# BrainControlBoard.net
KiCad netlist of a schematic drawn in EAGLE
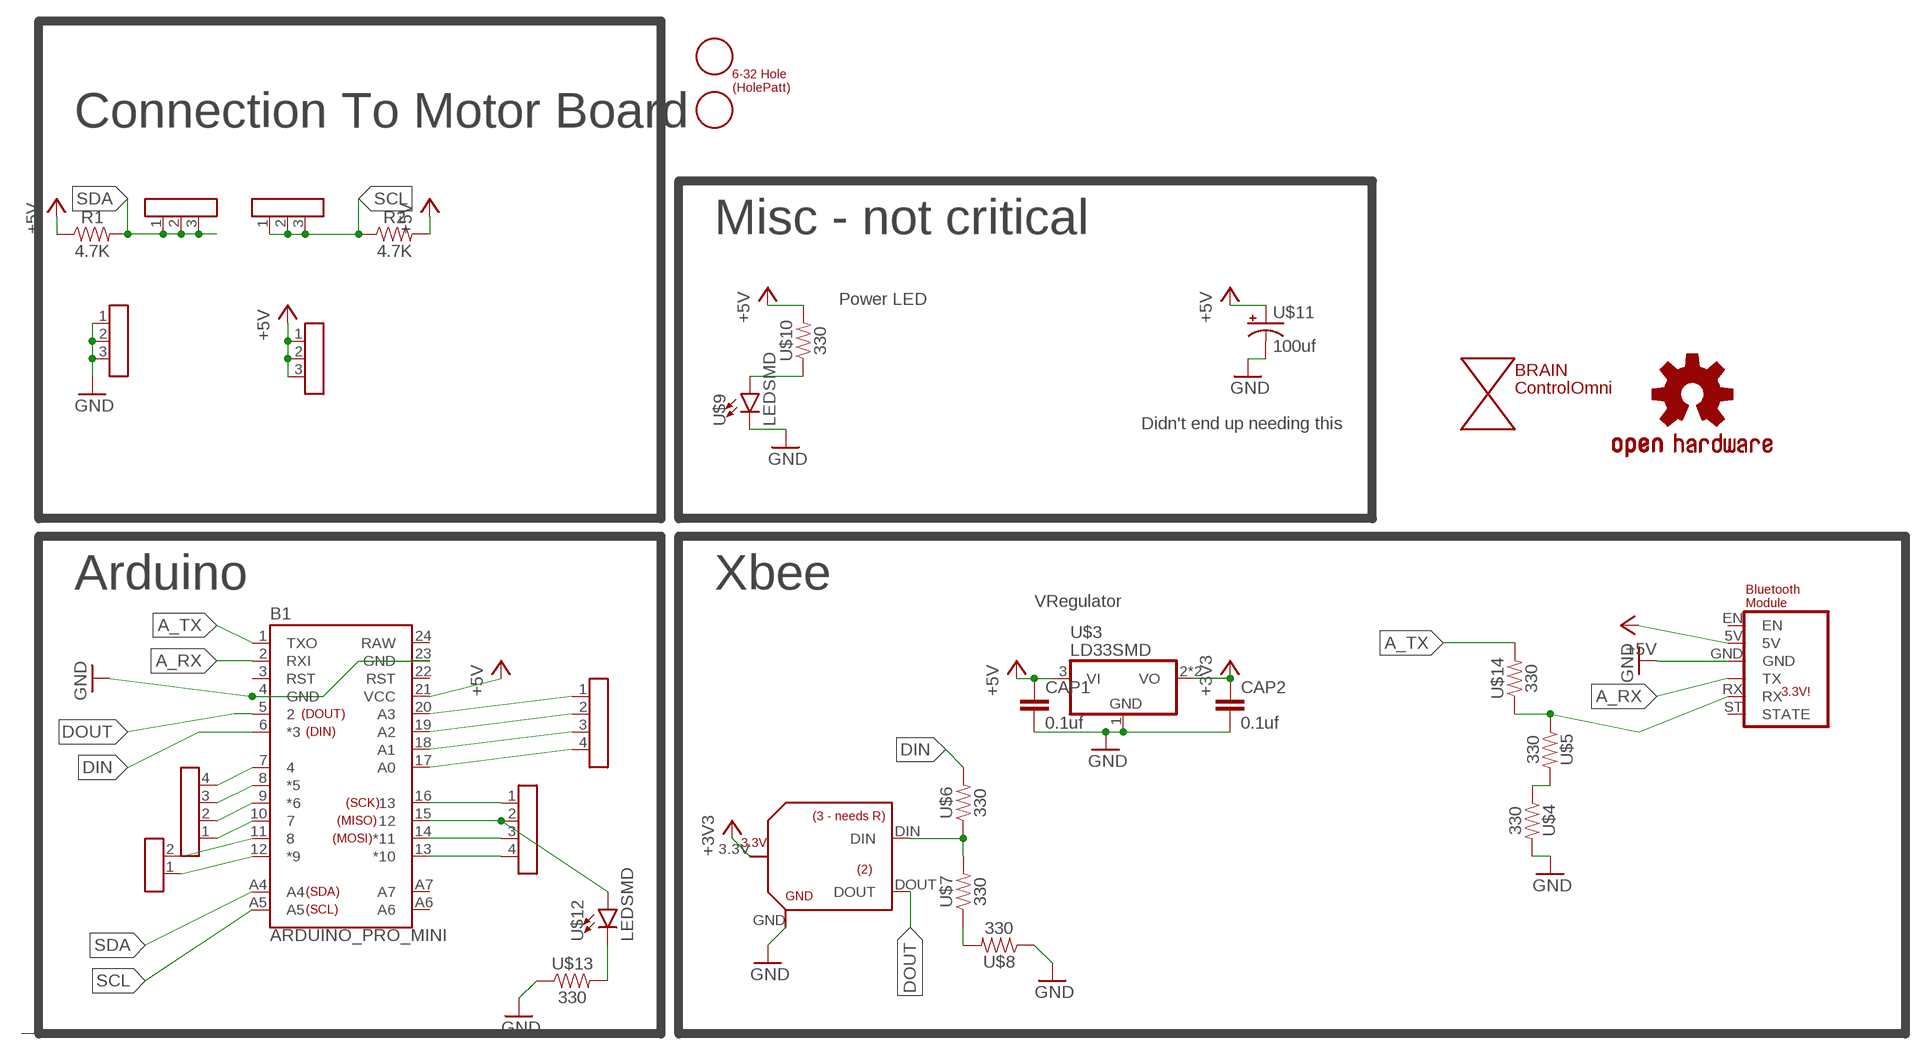
[diagram p0: schematic, sheet 1]

(export (version "E")
  (design (tool "Eeschema 10.0.6"))
  (components
    (comp (ref "B1")
      (value "ARDUINO_PRO_MINI")
      (footprint "eagle-import:ARDUINO_PRO_MINI")
      (libsource (lib "eagle-import") (part "ARDUINO_PRO_MINI"))
    )
    (comp (ref "BRAIN")
      (value "ControlOmni")
      (footprint "eagle-import:ANNOTATION")
      (libsource (lib "eagle-import") (part "ANNOTATION"))
    )
    (comp (ref "CAP1")
      (value "0.1uf")
      (footprint "eagle-import:C1206")
      (libsource (lib "eagle-import") (part "CAP_SMCAP"))
    )
    (comp (ref "CAP2")
      (value "0.1uf")
      (footprint "eagle-import:C1206")
      (libsource (lib "eagle-import") (part "CAP_SMCAP"))
    )
    (comp (ref "LOGO1")
      (value "OSHW-LOGOM")
      (footprint "eagle-import:OSHW-LOGO-M")
      (libsource (lib "eagle-import") (part "OSHW-LOGOM"))
    )
    (comp (ref "R1")
      (value "4.7K")
      (footprint "eagle-import:R1206")
      (libsource (lib "eagle-import") (part "RESISTORSMD"))
    )
    (comp (ref "R2")
      (value "4.7K")
      (footprint "eagle-import:R1206")
      (libsource (lib "eagle-import") (part "RESISTORSMD"))
    )
    (comp (ref "U$1")
      (value "BLUETOOTH")
      (footprint "eagle-import:BLUETOOTH")
      (libsource (lib "eagle-import") (part "BLUETOOTH"))
    )
    (comp (ref "U$2")
      (value "XBEE_BOUT")
      (footprint "eagle-import:XBEE_BOUT")
      (libsource (lib "eagle-import") (part "XBEE_BOUT"))
    )
    (comp (ref "U$3")
      (value "LD33SMD")
      (footprint "eagle-import:SOT223")
      (libsource (lib "eagle-import") (part "LD33SMD"))
    )
    (comp (ref "U$4")
      (value "330")
      (footprint "eagle-import:R1206")
      (libsource (lib "eagle-import") (part "RESISTORSMD"))
    )
    (comp (ref "U$5")
      (value "330")
      (footprint "eagle-import:R1206")
      (libsource (lib "eagle-import") (part "RESISTORSMD"))
    )
    (comp (ref "U$6")
      (value "330")
      (footprint "eagle-import:R1206")
      (libsource (lib "eagle-import") (part "RESISTORSMD"))
    )
    (comp (ref "U$7")
      (value "330")
      (footprint "eagle-import:R1206")
      (libsource (lib "eagle-import") (part "RESISTORSMD"))
    )
    (comp (ref "U$8")
      (value "330")
      (footprint "eagle-import:R1206")
      (libsource (lib "eagle-import") (part "RESISTORSMD"))
    )
    (comp (ref "U$9")
      (value "LEDSMD")
      (footprint "eagle-import:LED_SMD")
      (libsource (lib "eagle-import") (part "LEDSMD"))
    )
    (comp (ref "U$10")
      (value "330")
      (footprint "eagle-import:R1206")
      (libsource (lib "eagle-import") (part "RESISTORSMD"))
    )
    (comp (ref "U$11")
      (value "100uf")
      (footprint "eagle-import:CAP_E")
      (libsource (lib "eagle-import") (part "CAP_EMED"))
    )
    (comp (ref "U$12")
      (value "LEDSMD")
      (footprint "eagle-import:LED_SMD")
      (libsource (lib "eagle-import") (part "LEDSMD"))
    )
    (comp (ref "U$13")
      (value "330")
      (footprint "eagle-import:R1206")
      (libsource (lib "eagle-import") (part "RESISTORSMD"))
    )
    (comp (ref "U$14")
      (value "330")
      (footprint "eagle-import:R1206")
      (libsource (lib "eagle-import") (part "RESISTORSMD"))
    )
    (comp (ref "U$15")
      (value "3XHEADER")
      (footprint "eagle-import:3XHEADER")
      (libsource (lib "eagle-import") (part "3XHEADER"))
    )
    (comp (ref "U$16")
      (value "3XHEADER")
      (footprint "eagle-import:3XHEADER")
      (libsource (lib "eagle-import") (part "3XHEADER"))
    )
    (comp (ref "U$17")
      (value "3XHEADER")
      (footprint "eagle-import:3XHEADER")
      (libsource (lib "eagle-import") (part "3XHEADER"))
    )
    (comp (ref "U$18")
      (value "3XHEADER")
      (footprint "eagle-import:3XHEADER")
      (libsource (lib "eagle-import") (part "3XHEADER"))
    )
    (comp (ref "U$19")
      (value "4XHEADER")
      (footprint "eagle-import:4XHEADER")
      (libsource (lib "eagle-import") (part "4XHEADER"))
    )
    (comp (ref "U$20")
      (value "4XHEADER")
      (footprint "eagle-import:4XHEADER")
      (libsource (lib "eagle-import") (part "4XHEADER"))
    )
    (comp (ref "U$21")
      (value "2XHEADER")
      (footprint "eagle-import:2XHEADER")
      (libsource (lib "eagle-import") (part "2XHEADER"))
    )
    (comp (ref "U$22")
      (value "4XHEADER")
      (footprint "eagle-import:4XHEADER")
      (libsource (lib "eagle-import") (part "4XHEADER"))
    )
    (comp (ref "U$23")
      (value "632X2")
      (footprint "eagle-import:632X2")
      (libsource (lib "eagle-import") (part "632X2"))
    )
  )
  (nets
    (net (code "1") (name "+3V3") (class "Default")
      (node (ref "CAP2") (pin "1") (pinfunction "1_1") (pintype "passive"))
      (node (ref "U$2") (pin "3.3V") (pinfunction "3.3V_3.3V") (pintype "bidirectional"))
      (node (ref "U$3") (pin "2") (pinfunction "VO_2") (pintype "passive"))
      (node (ref "U$3") (pin "4") (pinfunction "VO_4") (pintype "passive"))
    )
    (net (code "2") (name "+5V") (class "Default")
      (node (ref "B1") (pin "21") (pinfunction "VCC_21") (pintype "power_in"))
      (node (ref "CAP1") (pin "1") (pinfunction "1_1") (pintype "passive"))
      (node (ref "R1") (pin "1") (pinfunction "1_1") (pintype "passive"))
      (node (ref "R2") (pin "2") (pinfunction "2_2") (pintype "passive"))
      (node (ref "U$1") (pin "5V") (pinfunction "5V_5V") (pintype "passive"))
      (node (ref "U$10") (pin "2") (pinfunction "2_2") (pintype "passive"))
      (node (ref "U$11") (pin "+") (pinfunction "+_+") (pintype "passive"))
      (node (ref "U$16") (pin "1") (pinfunction "1_1") (pintype "passive"))
      (node (ref "U$16") (pin "2") (pinfunction "2_2") (pintype "passive"))
      (node (ref "U$16") (pin "3") (pinfunction "3_3") (pintype "passive"))
      (node (ref "U$3") (pin "3") (pinfunction "VI_3") (pintype "input"))
    )
    (net (code "3") (name "/RAW") (class "Default")
      (node (ref "B1") (pin "24") (pinfunction "RAW_24") (pintype "power_in"))
    )
    (net (code "4") (name "A_RX") (class "Default")
      (node (ref "B1") (pin "2") (pinfunction "RXI_2") (pintype "bidirectional"))
      (node (ref "U$1") (pin "TX") (pinfunction "TX_TX") (pintype "passive"))
    )
    (net (code "5") (name "A_TX") (class "Default")
      (node (ref "B1") (pin "1") (pinfunction "TXO_1") (pintype "bidirectional"))
      (node (ref "U$14") (pin "2") (pinfunction "2_2") (pintype "passive"))
    )
    (net (code "6") (name "DIN") (class "Default")
      (node (ref "B1") (pin "6") (pinfunction "*3_6") (pintype "bidirectional"))
      (node (ref "U$6") (pin "2") (pinfunction "2_2") (pintype "passive"))
    )
    (net (code "7") (name "DOUT") (class "Default")
      (node (ref "B1") (pin "5") (pinfunction "2_5") (pintype "bidirectional"))
      (node (ref "U$2") (pin "DOUT") (pinfunction "DOUT_DOUT") (pintype "bidirectional"))
    )
    (net (code "8") (name "GND") (class "Default")
      (node (ref "B1") (pin "23") (pinfunction "GND_23") (pintype "power_in"))
      (node (ref "B1") (pin "4") (pinfunction "GND_4") (pintype "power_in"))
      (node (ref "CAP1") (pin "2") (pinfunction "2_2") (pintype "passive"))
      (node (ref "CAP2") (pin "2") (pinfunction "2_2") (pintype "passive"))
      (node (ref "U$1") (pin "GND") (pinfunction "GND_GND") (pintype "passive"))
      (node (ref "U$11") (pin "-") (pinfunction "-_-") (pintype "passive"))
      (node (ref "U$13") (pin "1") (pinfunction "1_1") (pintype "passive"))
      (node (ref "U$15") (pin "1") (pinfunction "1_1") (pintype "passive"))
      (node (ref "U$15") (pin "2") (pinfunction "2_2") (pintype "passive"))
      (node (ref "U$15") (pin "3") (pinfunction "3_3") (pintype "passive"))
      (node (ref "U$2") (pin "GND") (pinfunction "GND_GND") (pintype "bidirectional"))
      (node (ref "U$3") (pin "1") (pinfunction "GND_1") (pintype "passive"))
      (node (ref "U$4") (pin "2") (pinfunction "2_2") (pintype "passive"))
      (node (ref "U$8") (pin "1") (pinfunction "1_1") (pintype "passive"))
      (node (ref "U$9") (pin "C") (pinfunction "C_C") (pintype "passive"))
    )
    (net (code "9") (name "Net-(B1-*5)") (class "Default")
      (node (ref "B1") (pin "8") (pinfunction "*5_8") (pintype "bidirectional"))
      (node (ref "U$20") (pin "3") (pinfunction "3_3") (pintype "passive"))
    )
    (net (code "10") (name "Net-(B1-*6)") (class "Default")
      (node (ref "B1") (pin "9") (pinfunction "*6_9") (pintype "bidirectional"))
      (node (ref "U$20") (pin "2") (pinfunction "2_2") (pintype "passive"))
    )
    (net (code "11") (name "Net-(B1-*9)") (class "Default")
      (node (ref "B1") (pin "12") (pinfunction "*9_12") (pintype "bidirectional"))
      (node (ref "U$21") (pin "1") (pinfunction "1_1") (pintype "passive"))
    )
    (net (code "12") (name "Net-(B1-*10)") (class "Default")
      (node (ref "B1") (pin "13") (pinfunction "*10_13") (pintype "bidirectional"))
      (node (ref "U$22") (pin "4") (pinfunction "4_4") (pintype "passive"))
    )
    (net (code "13") (name "Net-(B1-*11)") (class "Default")
      (node (ref "B1") (pin "14") (pinfunction "*11_14") (pintype "bidirectional"))
      (node (ref "U$22") (pin "3") (pinfunction "3_3") (pintype "passive"))
    )
    (net (code "14") (name "Net-(B1-4)") (class "Default")
      (node (ref "B1") (pin "7") (pinfunction "4_7") (pintype "bidirectional"))
      (node (ref "U$20") (pin "4") (pinfunction "4_4") (pintype "passive"))
    )
    (net (code "15") (name "Net-(B1-7)") (class "Default")
      (node (ref "B1") (pin "10") (pinfunction "7_10") (pintype "bidirectional"))
      (node (ref "U$20") (pin "1") (pinfunction "1_1") (pintype "passive"))
    )
    (net (code "16") (name "Net-(B1-8)") (class "Default")
      (node (ref "B1") (pin "11") (pinfunction "8_11") (pintype "bidirectional"))
      (node (ref "U$21") (pin "2") (pinfunction "2_2") (pintype "passive"))
    )
    (net (code "17") (name "Net-(B1-12)") (class "Default")
      (node (ref "B1") (pin "15") (pinfunction "12_15") (pintype "bidirectional"))
      (node (ref "U$12") (pin "A") (pinfunction "A_A") (pintype "passive"))
      (node (ref "U$22") (pin "2") (pinfunction "2_2") (pintype "passive"))
    )
    (net (code "18") (name "Net-(B1-13)") (class "Default")
      (node (ref "B1") (pin "16") (pinfunction "13_16") (pintype "bidirectional"))
      (node (ref "U$22") (pin "1") (pinfunction "1_1") (pintype "passive"))
    )
    (net (code "19") (name "Net-(B1-A0)") (class "Default")
      (node (ref "B1") (pin "17") (pinfunction "A0_17") (pintype "bidirectional"))
      (node (ref "U$19") (pin "4") (pinfunction "4_4") (pintype "passive"))
    )
    (net (code "20") (name "Net-(B1-A1)") (class "Default")
      (node (ref "B1") (pin "18") (pinfunction "A1_18") (pintype "bidirectional"))
      (node (ref "U$19") (pin "3") (pinfunction "3_3") (pintype "passive"))
    )
    (net (code "21") (name "Net-(B1-A2)") (class "Default")
      (node (ref "B1") (pin "19") (pinfunction "A2_19") (pintype "bidirectional"))
      (node (ref "U$19") (pin "2") (pinfunction "2_2") (pintype "passive"))
    )
    (net (code "22") (name "Net-(B1-A3)") (class "Default")
      (node (ref "B1") (pin "20") (pinfunction "A3_20") (pintype "bidirectional"))
      (node (ref "U$19") (pin "1") (pinfunction "1_1") (pintype "passive"))
    )
    (net (code "23") (name "Net-(U$1-PadRX)") (class "Default")
      (node (ref "U$1") (pin "RX") (pinfunction "RX_RX") (pintype "passive"))
      (node (ref "U$14") (pin "1") (pinfunction "1_1") (pintype "passive"))
      (node (ref "U$5") (pin "1") (pinfunction "1_1") (pintype "passive"))
    )
    (net (code "24") (name "Net-(U$2-PadDIN)") (class "Default")
      (node (ref "U$2") (pin "DIN") (pinfunction "DIN_DIN") (pintype "bidirectional"))
      (node (ref "U$6") (pin "1") (pinfunction "1_1") (pintype "passive"))
      (node (ref "U$7") (pin "2") (pinfunction "2_2") (pintype "passive"))
    )
    (net (code "25") (name "Net-(U$4-Pad1)") (class "Default")
      (node (ref "U$4") (pin "1") (pinfunction "1_1") (pintype "passive"))
      (node (ref "U$5") (pin "2") (pinfunction "2_2") (pintype "passive"))
    )
    (net (code "26") (name "Net-(U$7-Pad1)") (class "Default")
      (node (ref "U$7") (pin "1") (pinfunction "1_1") (pintype "passive"))
      (node (ref "U$8") (pin "2") (pinfunction "2_2") (pintype "passive"))
    )
    (net (code "27") (name "Net-(U$10-Pad1)") (class "Default")
      (node (ref "U$10") (pin "1") (pinfunction "1_1") (pintype "passive"))
      (node (ref "U$9") (pin "A") (pinfunction "A_A") (pintype "passive"))
    )
    (net (code "28") (name "Net-(U$12-PadC)") (class "Default")
      (node (ref "U$12") (pin "C") (pinfunction "C_C") (pintype "passive"))
      (node (ref "U$13") (pin "2") (pinfunction "2_2") (pintype "passive"))
    )
    (net (code "29") (name "SCL") (class "Default")
      (node (ref "B1") (pin "A5") (pinfunction "A5_A5") (pintype "bidirectional"))
      (node (ref "R2") (pin "1") (pinfunction "1_1") (pintype "passive"))
      (node (ref "U$18") (pin "1") (pinfunction "1_1") (pintype "passive"))
      (node (ref "U$18") (pin "2") (pinfunction "2_2") (pintype "passive"))
      (node (ref "U$18") (pin "3") (pinfunction "3_3") (pintype "passive"))
    )
    (net (code "30") (name "SDA") (class "Default")
      (node (ref "B1") (pin "A4") (pinfunction "A4_A4") (pintype "bidirectional"))
      (node (ref "R1") (pin "2") (pinfunction "2_2") (pintype "passive"))
      (node (ref "U$17") (pin "1") (pinfunction "1_1") (pintype "passive"))
      (node (ref "U$17") (pin "2") (pinfunction "2_2") (pintype "passive"))
      (node (ref "U$17") (pin "3") (pinfunction "3_3") (pintype "passive"))
    )
    (net (code "31") (name "unconnected-(B1-PadA6)") (class "Default")
      (node (ref "B1") (pin "A6") (pinfunction "A6_A6") (pintype "bidirectional"))
    )
    (net (code "32") (name "unconnected-(B1-PadA7)") (class "Default")
      (node (ref "B1") (pin "A7") (pinfunction "A7_A7") (pintype "bidirectional"))
    )
    (net (code "33") (name "unconnected-(B1-RST-Pad3)") (class "Default")
      (node (ref "B1") (pin "3") (pinfunction "RST_3") (pintype "bidirectional"))
    )
    (net (code "34") (name "unconnected-(B1-RST-Pad22)") (class "Default")
      (node (ref "B1") (pin "22") (pinfunction "RST_22") (pintype "bidirectional"))
    )
    (net (code "35") (name "unconnected-(U$1-PadEN)") (class "Default")
      (node (ref "U$1") (pin "EN") (pinfunction "EN_EN") (pintype "passive"))
    )
    (net (code "36") (name "unconnected-(U$1-STATE-PadST)") (class "Default")
      (node (ref "U$1") (pin "ST") (pinfunction "STATE_ST") (pintype "passive"))
    )
  )
)
